# Relay_Sheet.net
KiCad netlist of a schematic drawn in Altium Designer
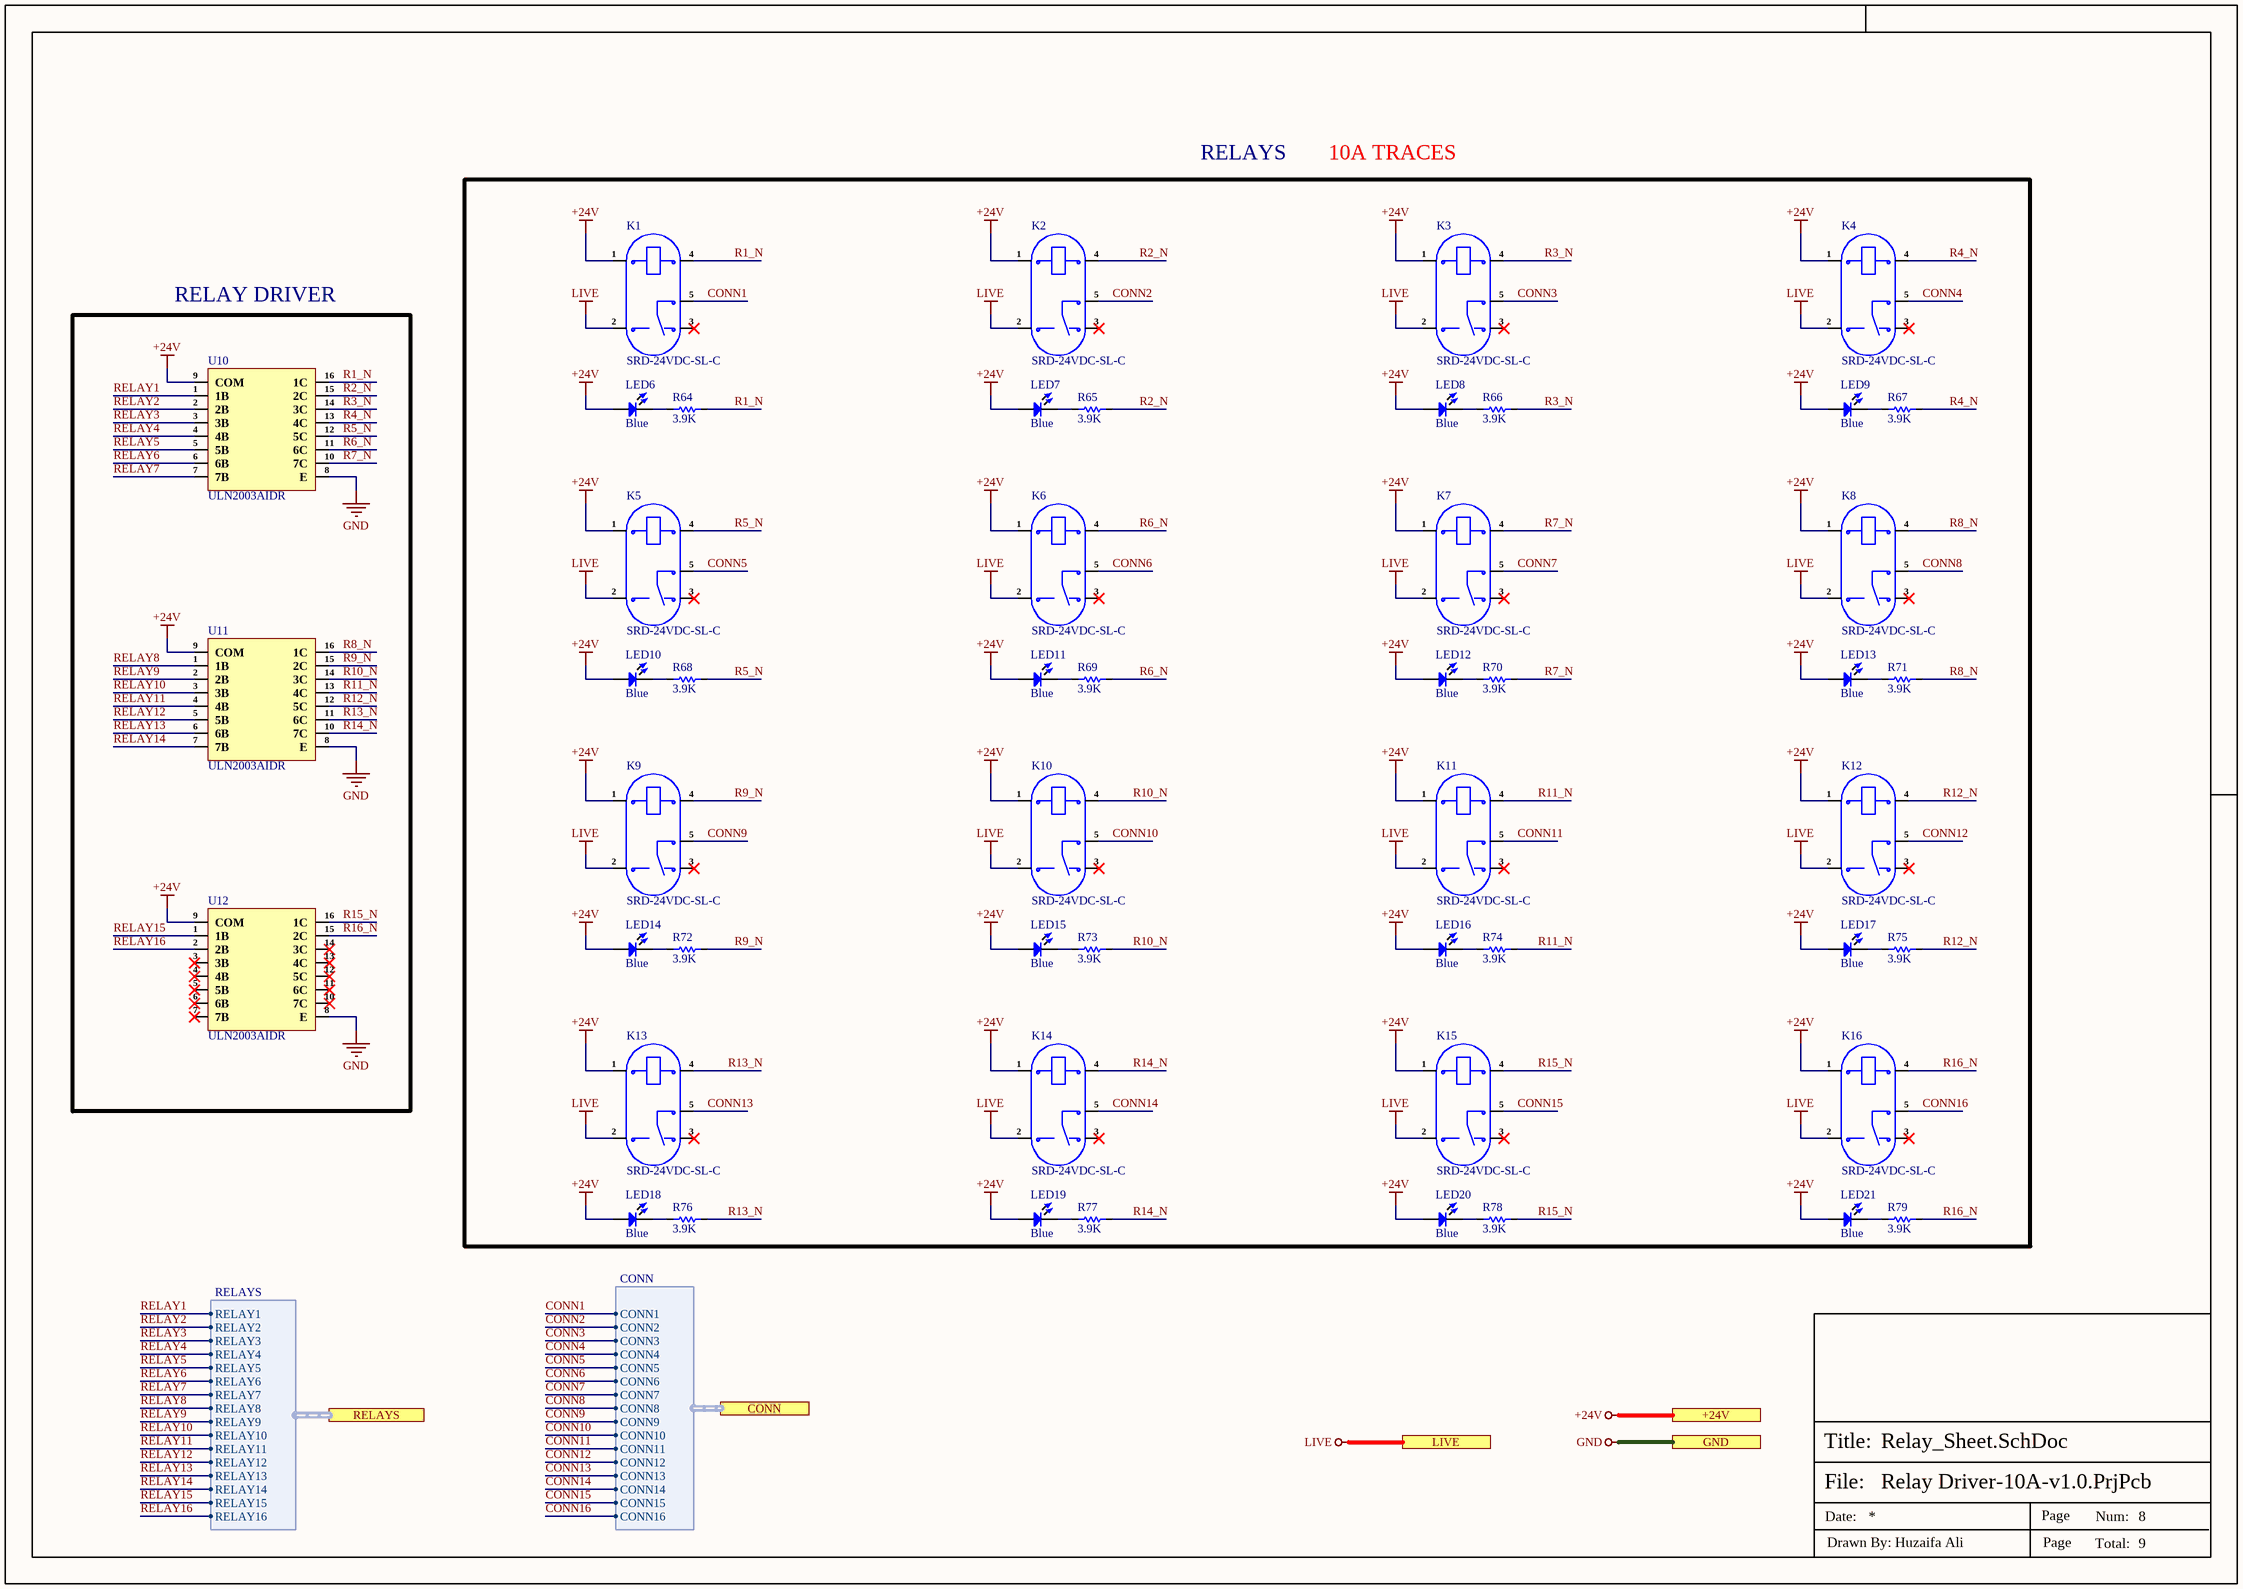
[diagram p0: Relay_Sheet.SchDoc]

(export (version "E")
  (design (tool "Eeschema 10.0.6"))
  (components
    (comp (ref "K1")
      (value "SRD-24VDC-SL-C")
      (footprint "SRD-24VDC-SL-C")
      (description "250V@AC 24V 15A SPDT (1 Form C) Plugin,15.6x19.2mm Power Relays ROHS")
      (fields (field (name "LCSC PART NUMBER") "C15840") (field (name "MANUFACTURER") "Ningbo Forward Relay"))
      (libsource (lib "eSpark Libraries") (part "SRD-24VDC-SL-C"))
    )
    (comp (ref "K2")
      (value "SRD-24VDC-SL-C")
      (footprint "SRD-24VDC-SL-C")
      (description "250V@AC 24V 15A SPDT (1 Form C) Plugin,15.6x19.2mm Power Relays ROHS")
      (fields (field (name "LCSC PART NUMBER") "C15840") (field (name "MANUFACTURER") "Ningbo Forward Relay"))
      (libsource (lib "eSpark Libraries") (part "SRD-24VDC-SL-C"))
    )
    (comp (ref "K3")
      (value "SRD-24VDC-SL-C")
      (footprint "SRD-24VDC-SL-C")
      (description "250V@AC 24V 15A SPDT (1 Form C) Plugin,15.6x19.2mm Power Relays ROHS")
      (fields (field (name "LCSC PART NUMBER") "C15840") (field (name "MANUFACTURER") "Ningbo Forward Relay"))
      (libsource (lib "eSpark Libraries") (part "SRD-24VDC-SL-C"))
    )
    (comp (ref "K4")
      (value "SRD-24VDC-SL-C")
      (footprint "SRD-24VDC-SL-C")
      (description "250V@AC 24V 15A SPDT (1 Form C) Plugin,15.6x19.2mm Power Relays ROHS")
      (fields (field (name "LCSC PART NUMBER") "C15840") (field (name "MANUFACTURER") "Ningbo Forward Relay"))
      (libsource (lib "eSpark Libraries") (part "SRD-24VDC-SL-C"))
    )
    (comp (ref "K5")
      (value "SRD-24VDC-SL-C")
      (footprint "SRD-24VDC-SL-C")
      (description "250V@AC 24V 15A SPDT (1 Form C) Plugin,15.6x19.2mm Power Relays ROHS")
      (fields (field (name "LCSC PART NUMBER") "C15840") (field (name "MANUFACTURER") "Ningbo Forward Relay"))
      (libsource (lib "eSpark Libraries") (part "SRD-24VDC-SL-C"))
    )
    (comp (ref "K6")
      (value "SRD-24VDC-SL-C")
      (footprint "SRD-24VDC-SL-C")
      (description "250V@AC 24V 15A SPDT (1 Form C) Plugin,15.6x19.2mm Power Relays ROHS")
      (fields (field (name "LCSC PART NUMBER") "C15840") (field (name "MANUFACTURER") "Ningbo Forward Relay"))
      (libsource (lib "eSpark Libraries") (part "SRD-24VDC-SL-C"))
    )
    (comp (ref "K7")
      (value "SRD-24VDC-SL-C")
      (footprint "SRD-24VDC-SL-C")
      (description "250V@AC 24V 15A SPDT (1 Form C) Plugin,15.6x19.2mm Power Relays ROHS")
      (fields (field (name "LCSC PART NUMBER") "C15840") (field (name "MANUFACTURER") "Ningbo Forward Relay"))
      (libsource (lib "eSpark Libraries") (part "SRD-24VDC-SL-C"))
    )
    (comp (ref "K8")
      (value "SRD-24VDC-SL-C")
      (footprint "SRD-24VDC-SL-C")
      (description "250V@AC 24V 15A SPDT (1 Form C) Plugin,15.6x19.2mm Power Relays ROHS")
      (fields (field (name "LCSC PART NUMBER") "C15840") (field (name "MANUFACTURER") "Ningbo Forward Relay"))
      (libsource (lib "eSpark Libraries") (part "SRD-24VDC-SL-C"))
    )
    (comp (ref "K9")
      (value "SRD-24VDC-SL-C")
      (footprint "SRD-24VDC-SL-C")
      (description "250V@AC 24V 15A SPDT (1 Form C) Plugin,15.6x19.2mm Power Relays ROHS")
      (fields (field (name "LCSC PART NUMBER") "C15840") (field (name "MANUFACTURER") "Ningbo Forward Relay"))
      (libsource (lib "eSpark Libraries") (part "SRD-24VDC-SL-C"))
    )
    (comp (ref "K10")
      (value "SRD-24VDC-SL-C")
      (footprint "SRD-24VDC-SL-C")
      (description "250V@AC 24V 15A SPDT (1 Form C) Plugin,15.6x19.2mm Power Relays ROHS")
      (fields (field (name "LCSC PART NUMBER") "C15840") (field (name "MANUFACTURER") "Ningbo Forward Relay"))
      (libsource (lib "eSpark Libraries") (part "SRD-24VDC-SL-C"))
    )
    (comp (ref "K11")
      (value "SRD-24VDC-SL-C")
      (footprint "SRD-24VDC-SL-C")
      (description "250V@AC 24V 15A SPDT (1 Form C) Plugin,15.6x19.2mm Power Relays ROHS")
      (fields (field (name "LCSC PART NUMBER") "C15840") (field (name "MANUFACTURER") "Ningbo Forward Relay"))
      (libsource (lib "eSpark Libraries") (part "SRD-24VDC-SL-C"))
    )
    (comp (ref "K12")
      (value "SRD-24VDC-SL-C")
      (footprint "SRD-24VDC-SL-C")
      (description "250V@AC 24V 15A SPDT (1 Form C) Plugin,15.6x19.2mm Power Relays ROHS")
      (fields (field (name "LCSC PART NUMBER") "C15840") (field (name "MANUFACTURER") "Ningbo Forward Relay"))
      (libsource (lib "eSpark Libraries") (part "SRD-24VDC-SL-C"))
    )
    (comp (ref "K13")
      (value "SRD-24VDC-SL-C")
      (footprint "SRD-24VDC-SL-C")
      (description "250V@AC 24V 15A SPDT (1 Form C) Plugin,15.6x19.2mm Power Relays ROHS")
      (fields (field (name "LCSC PART NUMBER") "C15840") (field (name "MANUFACTURER") "Ningbo Forward Relay"))
      (libsource (lib "eSpark Libraries") (part "SRD-24VDC-SL-C"))
    )
    (comp (ref "K14")
      (value "SRD-24VDC-SL-C")
      (footprint "SRD-24VDC-SL-C")
      (description "250V@AC 24V 15A SPDT (1 Form C) Plugin,15.6x19.2mm Power Relays ROHS")
      (fields (field (name "LCSC PART NUMBER") "C15840") (field (name "MANUFACTURER") "Ningbo Forward Relay"))
      (libsource (lib "eSpark Libraries") (part "SRD-24VDC-SL-C"))
    )
    (comp (ref "K15")
      (value "SRD-24VDC-SL-C")
      (footprint "SRD-24VDC-SL-C")
      (description "250V@AC 24V 15A SPDT (1 Form C) Plugin,15.6x19.2mm Power Relays ROHS")
      (fields (field (name "LCSC PART NUMBER") "C15840") (field (name "MANUFACTURER") "Ningbo Forward Relay"))
      (libsource (lib "eSpark Libraries") (part "SRD-24VDC-SL-C"))
    )
    (comp (ref "K16")
      (value "SRD-24VDC-SL-C")
      (footprint "SRD-24VDC-SL-C")
      (description "250V@AC 24V 15A SPDT (1 Form C) Plugin,15.6x19.2mm Power Relays ROHS")
      (fields (field (name "LCSC PART NUMBER") "C15840") (field (name "MANUFACTURER") "Ningbo Forward Relay"))
      (libsource (lib "eSpark Libraries") (part "SRD-24VDC-SL-C"))
    )
    (comp (ref "LED6")
      (value "Blue")
      (footprint "LED-0603")
      (description "blue 0603 Light Emitting Diodes (LED) ROHS")
      (fields
        (field (name "MANUFACTURER") "Foshan NationStar Optoelectronics")
        (field (name "MANUFACTURER PART NUMBER") "NCD0603B3")
      )
      (libsource (lib "eSpark Libraries") (part "NCD0603B3"))
    )
    (comp (ref "LED7")
      (value "Blue")
      (footprint "LED-0603")
      (description "blue 0603 Light Emitting Diodes (LED) ROHS")
      (fields
        (field (name "MANUFACTURER") "Foshan NationStar Optoelectronics")
        (field (name "MANUFACTURER PART NUMBER") "NCD0603B3")
      )
      (libsource (lib "eSpark Libraries") (part "NCD0603B3"))
    )
    (comp (ref "LED8")
      (value "Blue")
      (footprint "LED-0603")
      (description "blue 0603 Light Emitting Diodes (LED) ROHS")
      (fields
        (field (name "MANUFACTURER") "Foshan NationStar Optoelectronics")
        (field (name "MANUFACTURER PART NUMBER") "NCD0603B3")
      )
      (libsource (lib "eSpark Libraries") (part "NCD0603B3"))
    )
    (comp (ref "LED9")
      (value "Blue")
      (footprint "LED-0603")
      (description "blue 0603 Light Emitting Diodes (LED) ROHS")
      (fields
        (field (name "MANUFACTURER") "Foshan NationStar Optoelectronics")
        (field (name "MANUFACTURER PART NUMBER") "NCD0603B3")
      )
      (libsource (lib "eSpark Libraries") (part "NCD0603B3"))
    )
    (comp (ref "LED10")
      (value "Blue")
      (footprint "LED-0603")
      (description "blue 0603 Light Emitting Diodes (LED) ROHS")
      (fields
        (field (name "MANUFACTURER") "Foshan NationStar Optoelectronics")
        (field (name "MANUFACTURER PART NUMBER") "NCD0603B3")
      )
      (libsource (lib "eSpark Libraries") (part "NCD0603B3"))
    )
    (comp (ref "LED11")
      (value "Blue")
      (footprint "LED-0603")
      (description "blue 0603 Light Emitting Diodes (LED) ROHS")
      (fields
        (field (name "MANUFACTURER") "Foshan NationStar Optoelectronics")
        (field (name "MANUFACTURER PART NUMBER") "NCD0603B3")
      )
      (libsource (lib "eSpark Libraries") (part "NCD0603B3"))
    )
    (comp (ref "LED12")
      (value "Blue")
      (footprint "LED-0603")
      (description "blue 0603 Light Emitting Diodes (LED) ROHS")
      (fields
        (field (name "MANUFACTURER") "Foshan NationStar Optoelectronics")
        (field (name "MANUFACTURER PART NUMBER") "NCD0603B3")
      )
      (libsource (lib "eSpark Libraries") (part "NCD0603B3"))
    )
    (comp (ref "LED13")
      (value "Blue")
      (footprint "LED-0603")
      (description "blue 0603 Light Emitting Diodes (LED) ROHS")
      (fields
        (field (name "MANUFACTURER") "Foshan NationStar Optoelectronics")
        (field (name "MANUFACTURER PART NUMBER") "NCD0603B3")
      )
      (libsource (lib "eSpark Libraries") (part "NCD0603B3"))
    )
    (comp (ref "LED14")
      (value "Blue")
      (footprint "LED-0603")
      (description "blue 0603 Light Emitting Diodes (LED) ROHS")
      (fields
        (field (name "MANUFACTURER") "Foshan NationStar Optoelectronics")
        (field (name "MANUFACTURER PART NUMBER") "NCD0603B3")
      )
      (libsource (lib "eSpark Libraries") (part "NCD0603B3"))
    )
    (comp (ref "LED15")
      (value "Blue")
      (footprint "LED-0603")
      (description "blue 0603 Light Emitting Diodes (LED) ROHS")
      (fields
        (field (name "MANUFACTURER") "Foshan NationStar Optoelectronics")
        (field (name "MANUFACTURER PART NUMBER") "NCD0603B3")
      )
      (libsource (lib "eSpark Libraries") (part "NCD0603B3"))
    )
    (comp (ref "LED16")
      (value "Blue")
      (footprint "LED-0603")
      (description "blue 0603 Light Emitting Diodes (LED) ROHS")
      (fields
        (field (name "MANUFACTURER") "Foshan NationStar Optoelectronics")
        (field (name "MANUFACTURER PART NUMBER") "NCD0603B3")
      )
      (libsource (lib "eSpark Libraries") (part "NCD0603B3"))
    )
    (comp (ref "LED17")
      (value "Blue")
      (footprint "LED-0603")
      (description "blue 0603 Light Emitting Diodes (LED) ROHS")
      (fields
        (field (name "MANUFACTURER") "Foshan NationStar Optoelectronics")
        (field (name "MANUFACTURER PART NUMBER") "NCD0603B3")
      )
      (libsource (lib "eSpark Libraries") (part "NCD0603B3"))
    )
    (comp (ref "LED18")
      (value "Blue")
      (footprint "LED-0603")
      (description "blue 0603 Light Emitting Diodes (LED) ROHS")
      (fields
        (field (name "MANUFACTURER") "Foshan NationStar Optoelectronics")
        (field (name "MANUFACTURER PART NUMBER") "NCD0603B3")
      )
      (libsource (lib "eSpark Libraries") (part "NCD0603B3"))
    )
    (comp (ref "LED19")
      (value "Blue")
      (footprint "LED-0603")
      (description "blue 0603 Light Emitting Diodes (LED) ROHS")
      (fields
        (field (name "MANUFACTURER") "Foshan NationStar Optoelectronics")
        (field (name "MANUFACTURER PART NUMBER") "NCD0603B3")
      )
      (libsource (lib "eSpark Libraries") (part "NCD0603B3"))
    )
    (comp (ref "LED20")
      (value "Blue")
      (footprint "LED-0603")
      (description "blue 0603 Light Emitting Diodes (LED) ROHS")
      (fields
        (field (name "MANUFACTURER") "Foshan NationStar Optoelectronics")
        (field (name "MANUFACTURER PART NUMBER") "NCD0603B3")
      )
      (libsource (lib "eSpark Libraries") (part "NCD0603B3"))
    )
    (comp (ref "LED21")
      (value "Blue")
      (footprint "LED-0603")
      (description "blue 0603 Light Emitting Diodes (LED) ROHS")
      (fields
        (field (name "MANUFACTURER") "Foshan NationStar Optoelectronics")
        (field (name "MANUFACTURER PART NUMBER") "NCD0603B3")
      )
      (libsource (lib "eSpark Libraries") (part "NCD0603B3"))
    )
    (comp (ref "R64")
      (value "3.9K")
      (footprint "Res-0402")
      (description "RES 3.9K OHM 1% 1/16W 0402")
      (fields
        (field (name "MANUFACTURER") "Yageo")
        (field (name "MANUFACTURER PART NUMBER") "RC0402FR-073K9L")
      )
      (libsource (lib "eSpark Libraries") (part "RC0402FR-073K9L"))
    )
    (comp (ref "R65")
      (value "3.9K")
      (footprint "Res-0402")
      (description "RES 3.9K OHM 1% 1/16W 0402")
      (fields
        (field (name "MANUFACTURER") "Yageo")
        (field (name "MANUFACTURER PART NUMBER") "RC0402FR-073K9L")
      )
      (libsource (lib "eSpark Libraries") (part "RC0402FR-073K9L"))
    )
    (comp (ref "R66")
      (value "3.9K")
      (footprint "Res-0402")
      (description "RES 3.9K OHM 1% 1/16W 0402")
      (fields
        (field (name "MANUFACTURER") "Yageo")
        (field (name "MANUFACTURER PART NUMBER") "RC0402FR-073K9L")
      )
      (libsource (lib "eSpark Libraries") (part "RC0402FR-073K9L"))
    )
    (comp (ref "R67")
      (value "3.9K")
      (footprint "Res-0402")
      (description "RES 3.9K OHM 1% 1/16W 0402")
      (fields
        (field (name "MANUFACTURER") "Yageo")
        (field (name "MANUFACTURER PART NUMBER") "RC0402FR-073K9L")
      )
      (libsource (lib "eSpark Libraries") (part "RC0402FR-073K9L"))
    )
    (comp (ref "R68")
      (value "3.9K")
      (footprint "Res-0402")
      (description "RES 3.9K OHM 1% 1/16W 0402")
      (fields
        (field (name "MANUFACTURER") "Yageo")
        (field (name "MANUFACTURER PART NUMBER") "RC0402FR-073K9L")
      )
      (libsource (lib "eSpark Libraries") (part "RC0402FR-073K9L"))
    )
    (comp (ref "R69")
      (value "3.9K")
      (footprint "Res-0402")
      (description "RES 3.9K OHM 1% 1/16W 0402")
      (fields
        (field (name "MANUFACTURER") "Yageo")
        (field (name "MANUFACTURER PART NUMBER") "RC0402FR-073K9L")
      )
      (libsource (lib "eSpark Libraries") (part "RC0402FR-073K9L"))
    )
    (comp (ref "R70")
      (value "3.9K")
      (footprint "Res-0402")
      (description "RES 3.9K OHM 1% 1/16W 0402")
      (fields
        (field (name "MANUFACTURER") "Yageo")
        (field (name "MANUFACTURER PART NUMBER") "RC0402FR-073K9L")
      )
      (libsource (lib "eSpark Libraries") (part "RC0402FR-073K9L"))
    )
    (comp (ref "R71")
      (value "3.9K")
      (footprint "Res-0402")
      (description "RES 3.9K OHM 1% 1/16W 0402")
      (fields
        (field (name "MANUFACTURER") "Yageo")
        (field (name "MANUFACTURER PART NUMBER") "RC0402FR-073K9L")
      )
      (libsource (lib "eSpark Libraries") (part "RC0402FR-073K9L"))
    )
    (comp (ref "R72")
      (value "3.9K")
      (footprint "Res-0402")
      (description "RES 3.9K OHM 1% 1/16W 0402")
      (fields
        (field (name "MANUFACTURER") "Yageo")
        (field (name "MANUFACTURER PART NUMBER") "RC0402FR-073K9L")
      )
      (libsource (lib "eSpark Libraries") (part "RC0402FR-073K9L"))
    )
    (comp (ref "R73")
      (value "3.9K")
      (footprint "Res-0402")
      (description "RES 3.9K OHM 1% 1/16W 0402")
      (fields
        (field (name "MANUFACTURER") "Yageo")
        (field (name "MANUFACTURER PART NUMBER") "RC0402FR-073K9L")
      )
      (libsource (lib "eSpark Libraries") (part "RC0402FR-073K9L"))
    )
    (comp (ref "R74")
      (value "3.9K")
      (footprint "Res-0402")
      (description "RES 3.9K OHM 1% 1/16W 0402")
      (fields
        (field (name "MANUFACTURER") "Yageo")
        (field (name "MANUFACTURER PART NUMBER") "RC0402FR-073K9L")
      )
      (libsource (lib "eSpark Libraries") (part "RC0402FR-073K9L"))
    )
    (comp (ref "R75")
      (value "3.9K")
      (footprint "Res-0402")
      (description "RES 3.9K OHM 1% 1/16W 0402")
      (fields
        (field (name "MANUFACTURER") "Yageo")
        (field (name "MANUFACTURER PART NUMBER") "RC0402FR-073K9L")
      )
      (libsource (lib "eSpark Libraries") (part "RC0402FR-073K9L"))
    )
    (comp (ref "R76")
      (value "3.9K")
      (footprint "Res-0402")
      (description "RES 3.9K OHM 1% 1/16W 0402")
      (fields
        (field (name "MANUFACTURER") "Yageo")
        (field (name "MANUFACTURER PART NUMBER") "RC0402FR-073K9L")
      )
      (libsource (lib "eSpark Libraries") (part "RC0402FR-073K9L"))
    )
    (comp (ref "R77")
      (value "3.9K")
      (footprint "Res-0402")
      (description "RES 3.9K OHM 1% 1/16W 0402")
      (fields
        (field (name "MANUFACTURER") "Yageo")
        (field (name "MANUFACTURER PART NUMBER") "RC0402FR-073K9L")
      )
      (libsource (lib "eSpark Libraries") (part "RC0402FR-073K9L"))
    )
    (comp (ref "R78")
      (value "3.9K")
      (footprint "Res-0402")
      (description "RES 3.9K OHM 1% 1/16W 0402")
      (fields
        (field (name "MANUFACTURER") "Yageo")
        (field (name "MANUFACTURER PART NUMBER") "RC0402FR-073K9L")
      )
      (libsource (lib "eSpark Libraries") (part "RC0402FR-073K9L"))
    )
    (comp (ref "R79")
      (value "3.9K")
      (footprint "Res-0402")
      (description "RES 3.9K OHM 1% 1/16W 0402")
      (fields
        (field (name "MANUFACTURER") "Yageo")
        (field (name "MANUFACTURER PART NUMBER") "RC0402FR-073K9L")
      )
      (libsource (lib "eSpark Libraries") (part "RC0402FR-073K9L"))
    )
    (comp (ref "U10")
      (value "ULN2003AIDR")
      (footprint "16-SOIC (0.154\", 3.90mm Width)")
      (description "IC PWR RELAY 7NPN 1:1 16SOIC")
      (fields (field (name "MANUFACTURER") "Texas Instruments"))
      (libsource (lib "eSpark Libraries") (part "ULN2003AIDR"))
    )
    (comp (ref "U11")
      (value "ULN2003AIDR")
      (footprint "16-SOIC (0.154\", 3.90mm Width)")
      (description "IC PWR RELAY 7NPN 1:1 16SOIC")
      (fields (field (name "MANUFACTURER") "Texas Instruments"))
      (libsource (lib "eSpark Libraries") (part "ULN2003AIDR"))
    )
    (comp (ref "U12")
      (value "ULN2003AIDR")
      (footprint "16-SOIC (0.154\", 3.90mm Width)")
      (description "IC PWR RELAY 7NPN 1:1 16SOIC")
      (fields (field (name "MANUFACTURER") "Texas Instruments"))
      (libsource (lib "eSpark Libraries") (part "ULN2003AIDR"))
    )
  )
  (nets
    (net (code "3") (name "+24V") (class "Default")
      (node (ref "K1") (pin "1") (pinfunction "1_1") (pintype "passive"))
      (node (ref "K10") (pin "1") (pinfunction "1_1") (pintype "passive"))
      (node (ref "K11") (pin "1") (pinfunction "1_1") (pintype "passive"))
      (node (ref "K12") (pin "1") (pinfunction "1_1") (pintype "passive"))
      (node (ref "K13") (pin "1") (pinfunction "1_1") (pintype "passive"))
      (node (ref "K14") (pin "1") (pinfunction "1_1") (pintype "passive"))
      (node (ref "K15") (pin "1") (pinfunction "1_1") (pintype "passive"))
      (node (ref "K16") (pin "1") (pinfunction "1_1") (pintype "passive"))
      (node (ref "K2") (pin "1") (pinfunction "1_1") (pintype "passive"))
      (node (ref "K3") (pin "1") (pinfunction "1_1") (pintype "passive"))
      (node (ref "K4") (pin "1") (pinfunction "1_1") (pintype "passive"))
      (node (ref "K5") (pin "1") (pinfunction "1_1") (pintype "passive"))
      (node (ref "K6") (pin "1") (pinfunction "1_1") (pintype "passive"))
      (node (ref "K7") (pin "1") (pinfunction "1_1") (pintype "passive"))
      (node (ref "K8") (pin "1") (pinfunction "1_1") (pintype "passive"))
      (node (ref "K9") (pin "1") (pinfunction "1_1") (pintype "passive"))
      (node (ref "LED10") (pin "1") (pinfunction "1_1") (pintype "passive"))
      (node (ref "LED11") (pin "1") (pinfunction "1_1") (pintype "passive"))
      (node (ref "LED12") (pin "1") (pinfunction "1_1") (pintype "passive"))
      (node (ref "LED13") (pin "1") (pinfunction "1_1") (pintype "passive"))
      (node (ref "LED14") (pin "1") (pinfunction "1_1") (pintype "passive"))
      (node (ref "LED15") (pin "1") (pinfunction "1_1") (pintype "passive"))
      (node (ref "LED16") (pin "1") (pinfunction "1_1") (pintype "passive"))
      (node (ref "LED17") (pin "1") (pinfunction "1_1") (pintype "passive"))
      (node (ref "LED18") (pin "1") (pinfunction "1_1") (pintype "passive"))
      (node (ref "LED19") (pin "1") (pinfunction "1_1") (pintype "passive"))
      (node (ref "LED20") (pin "1") (pinfunction "1_1") (pintype "passive"))
      (node (ref "LED21") (pin "1") (pinfunction "1_1") (pintype "passive"))
      (node (ref "LED6") (pin "1") (pinfunction "1_1") (pintype "passive"))
      (node (ref "LED7") (pin "1") (pinfunction "1_1") (pintype "passive"))
      (node (ref "LED8") (pin "1") (pinfunction "1_1") (pintype "passive"))
      (node (ref "LED9") (pin "1") (pinfunction "1_1") (pintype "passive"))
      (node (ref "U10") (pin "9") (pinfunction "COM_9") (pintype "passive"))
      (node (ref "U11") (pin "9") (pinfunction "COM_9") (pintype "passive"))
      (node (ref "U12") (pin "9") (pinfunction "COM_9") (pintype "passive"))
    )
    (net (code "4") (name "/CONN1") (class "Default")
      (node (ref "K1") (pin "5") (pinfunction "5_5") (pintype "passive"))
    )
    (net (code "5") (name "/CONN2") (class "Default")
      (node (ref "K2") (pin "5") (pinfunction "5_5") (pintype "passive"))
    )
    (net (code "6") (name "/CONN3") (class "Default")
      (node (ref "K3") (pin "5") (pinfunction "5_5") (pintype "passive"))
    )
    (net (code "7") (name "/CONN4") (class "Default")
      (node (ref "K4") (pin "5") (pinfunction "5_5") (pintype "passive"))
    )
    (net (code "8") (name "/CONN5") (class "Default")
      (node (ref "K5") (pin "5") (pinfunction "5_5") (pintype "passive"))
    )
    (net (code "9") (name "/CONN6") (class "Default")
      (node (ref "K6") (pin "5") (pinfunction "5_5") (pintype "passive"))
    )
    (net (code "10") (name "/CONN7") (class "Default")
      (node (ref "K7") (pin "5") (pinfunction "5_5") (pintype "passive"))
    )
    (net (code "11") (name "/CONN8") (class "Default")
      (node (ref "K8") (pin "5") (pinfunction "5_5") (pintype "passive"))
    )
    (net (code "12") (name "/CONN9") (class "Default")
      (node (ref "K9") (pin "5") (pinfunction "5_5") (pintype "passive"))
    )
    (net (code "13") (name "/CONN10") (class "Default")
      (node (ref "K10") (pin "5") (pinfunction "5_5") (pintype "passive"))
    )
    (net (code "14") (name "/CONN11") (class "Default")
      (node (ref "K11") (pin "5") (pinfunction "5_5") (pintype "passive"))
    )
    (net (code "15") (name "/CONN12") (class "Default")
      (node (ref "K12") (pin "5") (pinfunction "5_5") (pintype "passive"))
    )
    (net (code "16") (name "/CONN13") (class "Default")
      (node (ref "K13") (pin "5") (pinfunction "5_5") (pintype "passive"))
    )
    (net (code "17") (name "/CONN14") (class "Default")
      (node (ref "K14") (pin "5") (pinfunction "5_5") (pintype "passive"))
    )
    (net (code "18") (name "/CONN15") (class "Default")
      (node (ref "K15") (pin "5") (pinfunction "5_5") (pintype "passive"))
    )
    (net (code "19") (name "/CONN16") (class "Default")
      (node (ref "K16") (pin "5") (pinfunction "5_5") (pintype "passive"))
    )
    (net (code "20") (name "/R1_N") (class "Default")
      (node (ref "K1") (pin "4") (pinfunction "4_4") (pintype "passive"))
      (node (ref "R64") (pin "2") (pinfunction "2_2") (pintype "passive"))
      (node (ref "U10") (pin "16") (pinfunction "1C_16") (pintype "passive"))
    )
    (net (code "21") (name "/R2_N") (class "Default")
      (node (ref "K2") (pin "4") (pinfunction "4_4") (pintype "passive"))
      (node (ref "R65") (pin "2") (pinfunction "2_2") (pintype "passive"))
      (node (ref "U10") (pin "15") (pinfunction "2C_15") (pintype "passive"))
    )
    (net (code "22") (name "/R3_N") (class "Default")
      (node (ref "K3") (pin "4") (pinfunction "4_4") (pintype "passive"))
      (node (ref "R66") (pin "2") (pinfunction "2_2") (pintype "passive"))
      (node (ref "U10") (pin "14") (pinfunction "3C_14") (pintype "passive"))
    )
    (net (code "23") (name "/R4_N") (class "Default")
      (node (ref "K4") (pin "4") (pinfunction "4_4") (pintype "passive"))
      (node (ref "R67") (pin "2") (pinfunction "2_2") (pintype "passive"))
      (node (ref "U10") (pin "13") (pinfunction "4C_13") (pintype "passive"))
    )
    (net (code "24") (name "/R5_N") (class "Default")
      (node (ref "K5") (pin "4") (pinfunction "4_4") (pintype "passive"))
      (node (ref "R68") (pin "2") (pinfunction "2_2") (pintype "passive"))
      (node (ref "U10") (pin "12") (pinfunction "5C_12") (pintype "passive"))
    )
    (net (code "25") (name "/R6_N") (class "Default")
      (node (ref "K6") (pin "4") (pinfunction "4_4") (pintype "passive"))
      (node (ref "R69") (pin "2") (pinfunction "2_2") (pintype "passive"))
      (node (ref "U10") (pin "11") (pinfunction "6C_11") (pintype "passive"))
    )
    (net (code "26") (name "/R7_N") (class "Default")
      (node (ref "K7") (pin "4") (pinfunction "4_4") (pintype "passive"))
      (node (ref "R70") (pin "2") (pinfunction "2_2") (pintype "passive"))
      (node (ref "U10") (pin "10") (pinfunction "7C_10") (pintype "passive"))
    )
    (net (code "27") (name "/R8_N") (class "Default")
      (node (ref "K8") (pin "4") (pinfunction "4_4") (pintype "passive"))
      (node (ref "R71") (pin "2") (pinfunction "2_2") (pintype "passive"))
      (node (ref "U11") (pin "16") (pinfunction "1C_16") (pintype "passive"))
    )
    (net (code "28") (name "/R9_N") (class "Default")
      (node (ref "K9") (pin "4") (pinfunction "4_4") (pintype "passive"))
      (node (ref "R72") (pin "2") (pinfunction "2_2") (pintype "passive"))
      (node (ref "U11") (pin "15") (pinfunction "2C_15") (pintype "passive"))
    )
    (net (code "29") (name "/R10_N") (class "Default")
      (node (ref "K10") (pin "4") (pinfunction "4_4") (pintype "passive"))
      (node (ref "R73") (pin "2") (pinfunction "2_2") (pintype "passive"))
      (node (ref "U11") (pin "14") (pinfunction "3C_14") (pintype "passive"))
    )
    (net (code "30") (name "/R11_N") (class "Default")
      (node (ref "K11") (pin "4") (pinfunction "4_4") (pintype "passive"))
      (node (ref "R74") (pin "2") (pinfunction "2_2") (pintype "passive"))
      (node (ref "U11") (pin "13") (pinfunction "4C_13") (pintype "passive"))
    )
    (net (code "31") (name "/R12_N") (class "Default")
      (node (ref "K12") (pin "4") (pinfunction "4_4") (pintype "passive"))
      (node (ref "R75") (pin "2") (pinfunction "2_2") (pintype "passive"))
      (node (ref "U11") (pin "12") (pinfunction "5C_12") (pintype "passive"))
    )
    (net (code "32") (name "/R13_N") (class "Default")
      (node (ref "K13") (pin "4") (pinfunction "4_4") (pintype "passive"))
      (node (ref "R76") (pin "2") (pinfunction "2_2") (pintype "passive"))
      (node (ref "U11") (pin "11") (pinfunction "6C_11") (pintype "passive"))
    )
    (net (code "33") (name "/R14_N") (class "Default")
      (node (ref "K14") (pin "4") (pinfunction "4_4") (pintype "passive"))
      (node (ref "R77") (pin "2") (pinfunction "2_2") (pintype "passive"))
      (node (ref "U11") (pin "10") (pinfunction "7C_10") (pintype "passive"))
    )
    (net (code "34") (name "/R15_N") (class "Default")
      (node (ref "K15") (pin "4") (pinfunction "4_4") (pintype "passive"))
      (node (ref "R78") (pin "2") (pinfunction "2_2") (pintype "passive"))
      (node (ref "U12") (pin "16") (pinfunction "1C_16") (pintype "passive"))
    )
    (net (code "35") (name "/R16_N") (class "Default")
      (node (ref "K16") (pin "4") (pinfunction "4_4") (pintype "passive"))
      (node (ref "R79") (pin "2") (pinfunction "2_2") (pintype "passive"))
      (node (ref "U12") (pin "15") (pinfunction "2C_15") (pintype "passive"))
    )
    (net (code "36") (name "/RELAY1") (class "Default")
      (node (ref "U10") (pin "1") (pinfunction "1B_1") (pintype "passive"))
    )
    (net (code "37") (name "/RELAY2") (class "Default")
      (node (ref "U10") (pin "2") (pinfunction "2B_2") (pintype "passive"))
    )
    (net (code "38") (name "/RELAY3") (class "Default")
      (node (ref "U10") (pin "3") (pinfunction "3B_3") (pintype "passive"))
    )
    (net (code "39") (name "/RELAY4") (class "Default")
      (node (ref "U10") (pin "4") (pinfunction "4B_4") (pintype "passive"))
    )
    (net (code "40") (name "/RELAY5") (class "Default")
      (node (ref "U10") (pin "5") (pinfunction "5B_5") (pintype "passive"))
    )
    (net (code "41") (name "/RELAY6") (class "Default")
      (node (ref "U10") (pin "6") (pinfunction "6B_6") (pintype "passive"))
    )
    (net (code "42") (name "/RELAY7") (class "Default")
      (node (ref "U10") (pin "7") (pinfunction "7B_7") (pintype "passive"))
    )
    (net (code "43") (name "/RELAY8") (class "Default")
      (node (ref "U11") (pin "1") (pinfunction "1B_1") (pintype "passive"))
    )
    (net (code "44") (name "/RELAY9") (class "Default")
      (node (ref "U11") (pin "2") (pinfunction "2B_2") (pintype "passive"))
    )
    (net (code "45") (name "/RELAY10") (class "Default")
      (node (ref "U11") (pin "3") (pinfunction "3B_3") (pintype "passive"))
    )
    (net (code "46") (name "/RELAY11") (class "Default")
      (node (ref "U11") (pin "4") (pinfunction "4B_4") (pintype "passive"))
    )
    (net (code "47") (name "/RELAY12") (class "Default")
      (node (ref "U11") (pin "5") (pinfunction "5B_5") (pintype "passive"))
    )
    (net (code "48") (name "/RELAY13") (class "Default")
      (node (ref "U11") (pin "6") (pinfunction "6B_6") (pintype "passive"))
    )
    (net (code "49") (name "/RELAY14") (class "Default")
      (node (ref "U11") (pin "7") (pinfunction "7B_7") (pintype "passive"))
    )
    (net (code "50") (name "/RELAY15") (class "Default")
      (node (ref "U12") (pin "1") (pinfunction "1B_1") (pintype "passive"))
    )
    (net (code "51") (name "/RELAY16") (class "Default")
      (node (ref "U12") (pin "2") (pinfunction "2B_2") (pintype "passive"))
    )
    (net (code "54") (name "GND") (class "Default")
      (node (ref "U10") (pin "8") (pinfunction "E_8") (pintype "passive"))
      (node (ref "U11") (pin "8") (pinfunction "E_8") (pintype "passive"))
      (node (ref "U12") (pin "8") (pinfunction "E_8") (pintype "passive"))
    )
    (net (code "55") (name "LIVE") (class "Default")
      (node (ref "K1") (pin "2") (pinfunction "2_2") (pintype "passive"))
      (node (ref "K10") (pin "2") (pinfunction "2_2") (pintype "passive"))
      (node (ref "K11") (pin "2") (pinfunction "2_2") (pintype "passive"))
      (node (ref "K12") (pin "2") (pinfunction "2_2") (pintype "passive"))
      (node (ref "K13") (pin "2") (pinfunction "2_2") (pintype "passive"))
      (node (ref "K14") (pin "2") (pinfunction "2_2") (pintype "passive"))
      (node (ref "K15") (pin "2") (pinfunction "2_2") (pintype "passive"))
      (node (ref "K16") (pin "2") (pinfunction "2_2") (pintype "passive"))
      (node (ref "K2") (pin "2") (pinfunction "2_2") (pintype "passive"))
      (node (ref "K3") (pin "2") (pinfunction "2_2") (pintype "passive"))
      (node (ref "K4") (pin "2") (pinfunction "2_2") (pintype "passive"))
      (node (ref "K5") (pin "2") (pinfunction "2_2") (pintype "passive"))
      (node (ref "K6") (pin "2") (pinfunction "2_2") (pintype "passive"))
      (node (ref "K7") (pin "2") (pinfunction "2_2") (pintype "passive"))
      (node (ref "K8") (pin "2") (pinfunction "2_2") (pintype "passive"))
      (node (ref "K9") (pin "2") (pinfunction "2_2") (pintype "passive"))
    )
    (net (code "56") (name "Net-(LED6-Pad2)") (class "Default")
      (node (ref "LED6") (pin "2") (pinfunction "2_2") (pintype "passive"))
      (node (ref "R64") (pin "1") (pinfunction "1_1") (pintype "passive"))
    )
    (net (code "57") (name "Net-(LED7-Pad2)") (class "Default")
      (node (ref "LED7") (pin "2") (pinfunction "2_2") (pintype "passive"))
      (node (ref "R65") (pin "1") (pinfunction "1_1") (pintype "passive"))
    )
    (net (code "58") (name "Net-(LED8-Pad2)") (class "Default")
      (node (ref "LED8") (pin "2") (pinfunction "2_2") (pintype "passive"))
      (node (ref "R66") (pin "1") (pinfunction "1_1") (pintype "passive"))
    )
    (net (code "59") (name "Net-(LED9-Pad2)") (class "Default")
      (node (ref "LED9") (pin "2") (pinfunction "2_2") (pintype "passive"))
      (node (ref "R67") (pin "1") (pinfunction "1_1") (pintype "passive"))
    )
    (net (code "60") (name "Net-(LED10-Pad2)") (class "Default")
      (node (ref "LED10") (pin "2") (pinfunction "2_2") (pintype "passive"))
      (node (ref "R68") (pin "1") (pinfunction "1_1") (pintype "passive"))
    )
    (net (code "61") (name "Net-(LED11-Pad2)") (class "Default")
      (node (ref "LED11") (pin "2") (pinfunction "2_2") (pintype "passive"))
      (node (ref "R69") (pin "1") (pinfunction "1_1") (pintype "passive"))
    )
    (net (code "62") (name "Net-(LED12-Pad2)") (class "Default")
      (node (ref "LED12") (pin "2") (pinfunction "2_2") (pintype "passive"))
      (node (ref "R70") (pin "1") (pinfunction "1_1") (pintype "passive"))
    )
    (net (code "63") (name "Net-(LED13-Pad2)") (class "Default")
      (node (ref "LED13") (pin "2") (pinfunction "2_2") (pintype "passive"))
      (node (ref "R71") (pin "1") (pinfunction "1_1") (pintype "passive"))
    )
    (net (code "64") (name "Net-(LED14-Pad2)") (class "Default")
      (node (ref "LED14") (pin "2") (pinfunction "2_2") (pintype "passive"))
      (node (ref "R72") (pin "1") (pinfunction "1_1") (pintype "passive"))
    )
    (net (code "65") (name "Net-(LED15-Pad2)") (class "Default")
      (node (ref "LED15") (pin "2") (pinfunction "2_2") (pintype "passive"))
      (node (ref "R73") (pin "1") (pinfunction "1_1") (pintype "passive"))
    )
    (net (code "66") (name "Net-(LED16-Pad2)") (class "Default")
      (node (ref "LED16") (pin "2") (pinfunction "2_2") (pintype "passive"))
      (node (ref "R74") (pin "1") (pinfunction "1_1") (pintype "passive"))
    )
    (net (code "67") (name "Net-(LED17-Pad2)") (class "Default")
      (node (ref "LED17") (pin "2") (pinfunction "2_2") (pintype "passive"))
      (node (ref "R75") (pin "1") (pinfunction "1_1") (pintype "passive"))
    )
    (net (code "68") (name "Net-(LED18-Pad2)") (class "Default")
      (node (ref "LED18") (pin "2") (pinfunction "2_2") (pintype "passive"))
      (node (ref "R76") (pin "1") (pinfunction "1_1") (pintype "passive"))
    )
    (net (code "69") (name "Net-(LED19-Pad2)") (class "Default")
      (node (ref "LED19") (pin "2") (pinfunction "2_2") (pintype "passive"))
      (node (ref "R77") (pin "1") (pinfunction "1_1") (pintype "passive"))
    )
    (net (code "70") (name "Net-(LED20-Pad2)") (class "Default")
      (node (ref "LED20") (pin "2") (pinfunction "2_2") (pintype "passive"))
      (node (ref "R78") (pin "1") (pinfunction "1_1") (pintype "passive"))
    )
    (net (code "71") (name "Net-(LED21-Pad2)") (class "Default")
      (node (ref "LED21") (pin "2") (pinfunction "2_2") (pintype "passive"))
      (node (ref "R79") (pin "1") (pinfunction "1_1") (pintype "passive"))
    )
    (net (code "72") (name "unconnected-(K1-Pad3)") (class "Default")
      (node (ref "K1") (pin "3") (pinfunction "3_3") (pintype "passive+no_connect"))
    )
    (net (code "73") (name "unconnected-(K2-Pad3)") (class "Default")
      (node (ref "K2") (pin "3") (pinfunction "3_3") (pintype "passive+no_connect"))
    )
    (net (code "74") (name "unconnected-(K3-Pad3)") (class "Default")
      (node (ref "K3") (pin "3") (pinfunction "3_3") (pintype "passive+no_connect"))
    )
    (net (code "75") (name "unconnected-(K4-Pad3)") (class "Default")
      (node (ref "K4") (pin "3") (pinfunction "3_3") (pintype "passive+no_connect"))
    )
    (net (code "76") (name "unconnected-(K5-Pad3)") (class "Default")
      (node (ref "K5") (pin "3") (pinfunction "3_3") (pintype "passive+no_connect"))
    )
    (net (code "77") (name "unconnected-(K6-Pad3)") (class "Default")
      (node (ref "K6") (pin "3") (pinfunction "3_3") (pintype "passive+no_connect"))
    )
    (net (code "78") (name "unconnected-(K7-Pad3)") (class "Default")
      (node (ref "K7") (pin "3") (pinfunction "3_3") (pintype "passive+no_connect"))
    )
    (net (code "79") (name "unconnected-(K8-Pad3)") (class "Default")
      (node (ref "K8") (pin "3") (pinfunction "3_3") (pintype "passive+no_connect"))
    )
    (net (code "80") (name "unconnected-(K9-Pad3)") (class "Default")
      (node (ref "K9") (pin "3") (pinfunction "3_3") (pintype "passive+no_connect"))
    )
    (net (code "81") (name "unconnected-(K10-Pad3)") (class "Default")
      (node (ref "K10") (pin "3") (pinfunction "3_3") (pintype "passive+no_connect"))
    )
    (net (code "82") (name "unconnected-(K11-Pad3)") (class "Default")
      (node (ref "K11") (pin "3") (pinfunction "3_3") (pintype "passive+no_connect"))
    )
    (net (code "83") (name "unconnected-(K12-Pad3)") (class "Default")
      (node (ref "K12") (pin "3") (pinfunction "3_3") (pintype "passive+no_connect"))
    )
    (net (code "84") (name "unconnected-(K13-Pad3)") (class "Default")
      (node (ref "K13") (pin "3") (pinfunction "3_3") (pintype "passive+no_connect"))
    )
    (net (code "85") (name "unconnected-(K14-Pad3)") (class "Default")
      (node (ref "K14") (pin "3") (pinfunction "3_3") (pintype "passive+no_connect"))
    )
    (net (code "86") (name "unconnected-(K15-Pad3)") (class "Default")
      (node (ref "K15") (pin "3") (pinfunction "3_3") (pintype "passive+no_connect"))
    )
    (net (code "87") (name "unconnected-(K16-Pad3)") (class "Default")
      (node (ref "K16") (pin "3") (pinfunction "3_3") (pintype "passive+no_connect"))
    )
    (net (code "88") (name "unconnected-(U12-3B-Pad3)") (class "Default")
      (node (ref "U12") (pin "3") (pinfunction "3B_3") (pintype "passive+no_connect"))
    )
    (net (code "89") (name "unconnected-(U12-3C-Pad14)") (class "Default")
      (node (ref "U12") (pin "14") (pinfunction "3C_14") (pintype "passive+no_connect"))
    )
    (net (code "90") (name "unconnected-(U12-4B-Pad4)") (class "Default")
      (node (ref "U12") (pin "4") (pinfunction "4B_4") (pintype "passive+no_connect"))
    )
    (net (code "91") (name "unconnected-(U12-4C-Pad13)") (class "Default")
      (node (ref "U12") (pin "13") (pinfunction "4C_13") (pintype "passive+no_connect"))
    )
    (net (code "92") (name "unconnected-(U12-5B-Pad5)") (class "Default")
      (node (ref "U12") (pin "5") (pinfunction "5B_5") (pintype "passive+no_connect"))
    )
    (net (code "93") (name "unconnected-(U12-5C-Pad12)") (class "Default")
      (node (ref "U12") (pin "12") (pinfunction "5C_12") (pintype "passive+no_connect"))
    )
    (net (code "94") (name "unconnected-(U12-6B-Pad6)") (class "Default")
      (node (ref "U12") (pin "6") (pinfunction "6B_6") (pintype "passive+no_connect"))
    )
    (net (code "95") (name "unconnected-(U12-6C-Pad11)") (class "Default")
      (node (ref "U12") (pin "11") (pinfunction "6C_11") (pintype "passive+no_connect"))
    )
    (net (code "96") (name "unconnected-(U12-7B-Pad7)") (class "Default")
      (node (ref "U12") (pin "7") (pinfunction "7B_7") (pintype "passive+no_connect"))
    )
    (net (code "97") (name "unconnected-(U12-7C-Pad10)") (class "Default")
      (node (ref "U12") (pin "10") (pinfunction "7C_10") (pintype "passive+no_connect"))
    )
  )
)
